# 1-Schematic_PCB__Board.net
KiCad netlist of a schematic drawn in EasyEDA
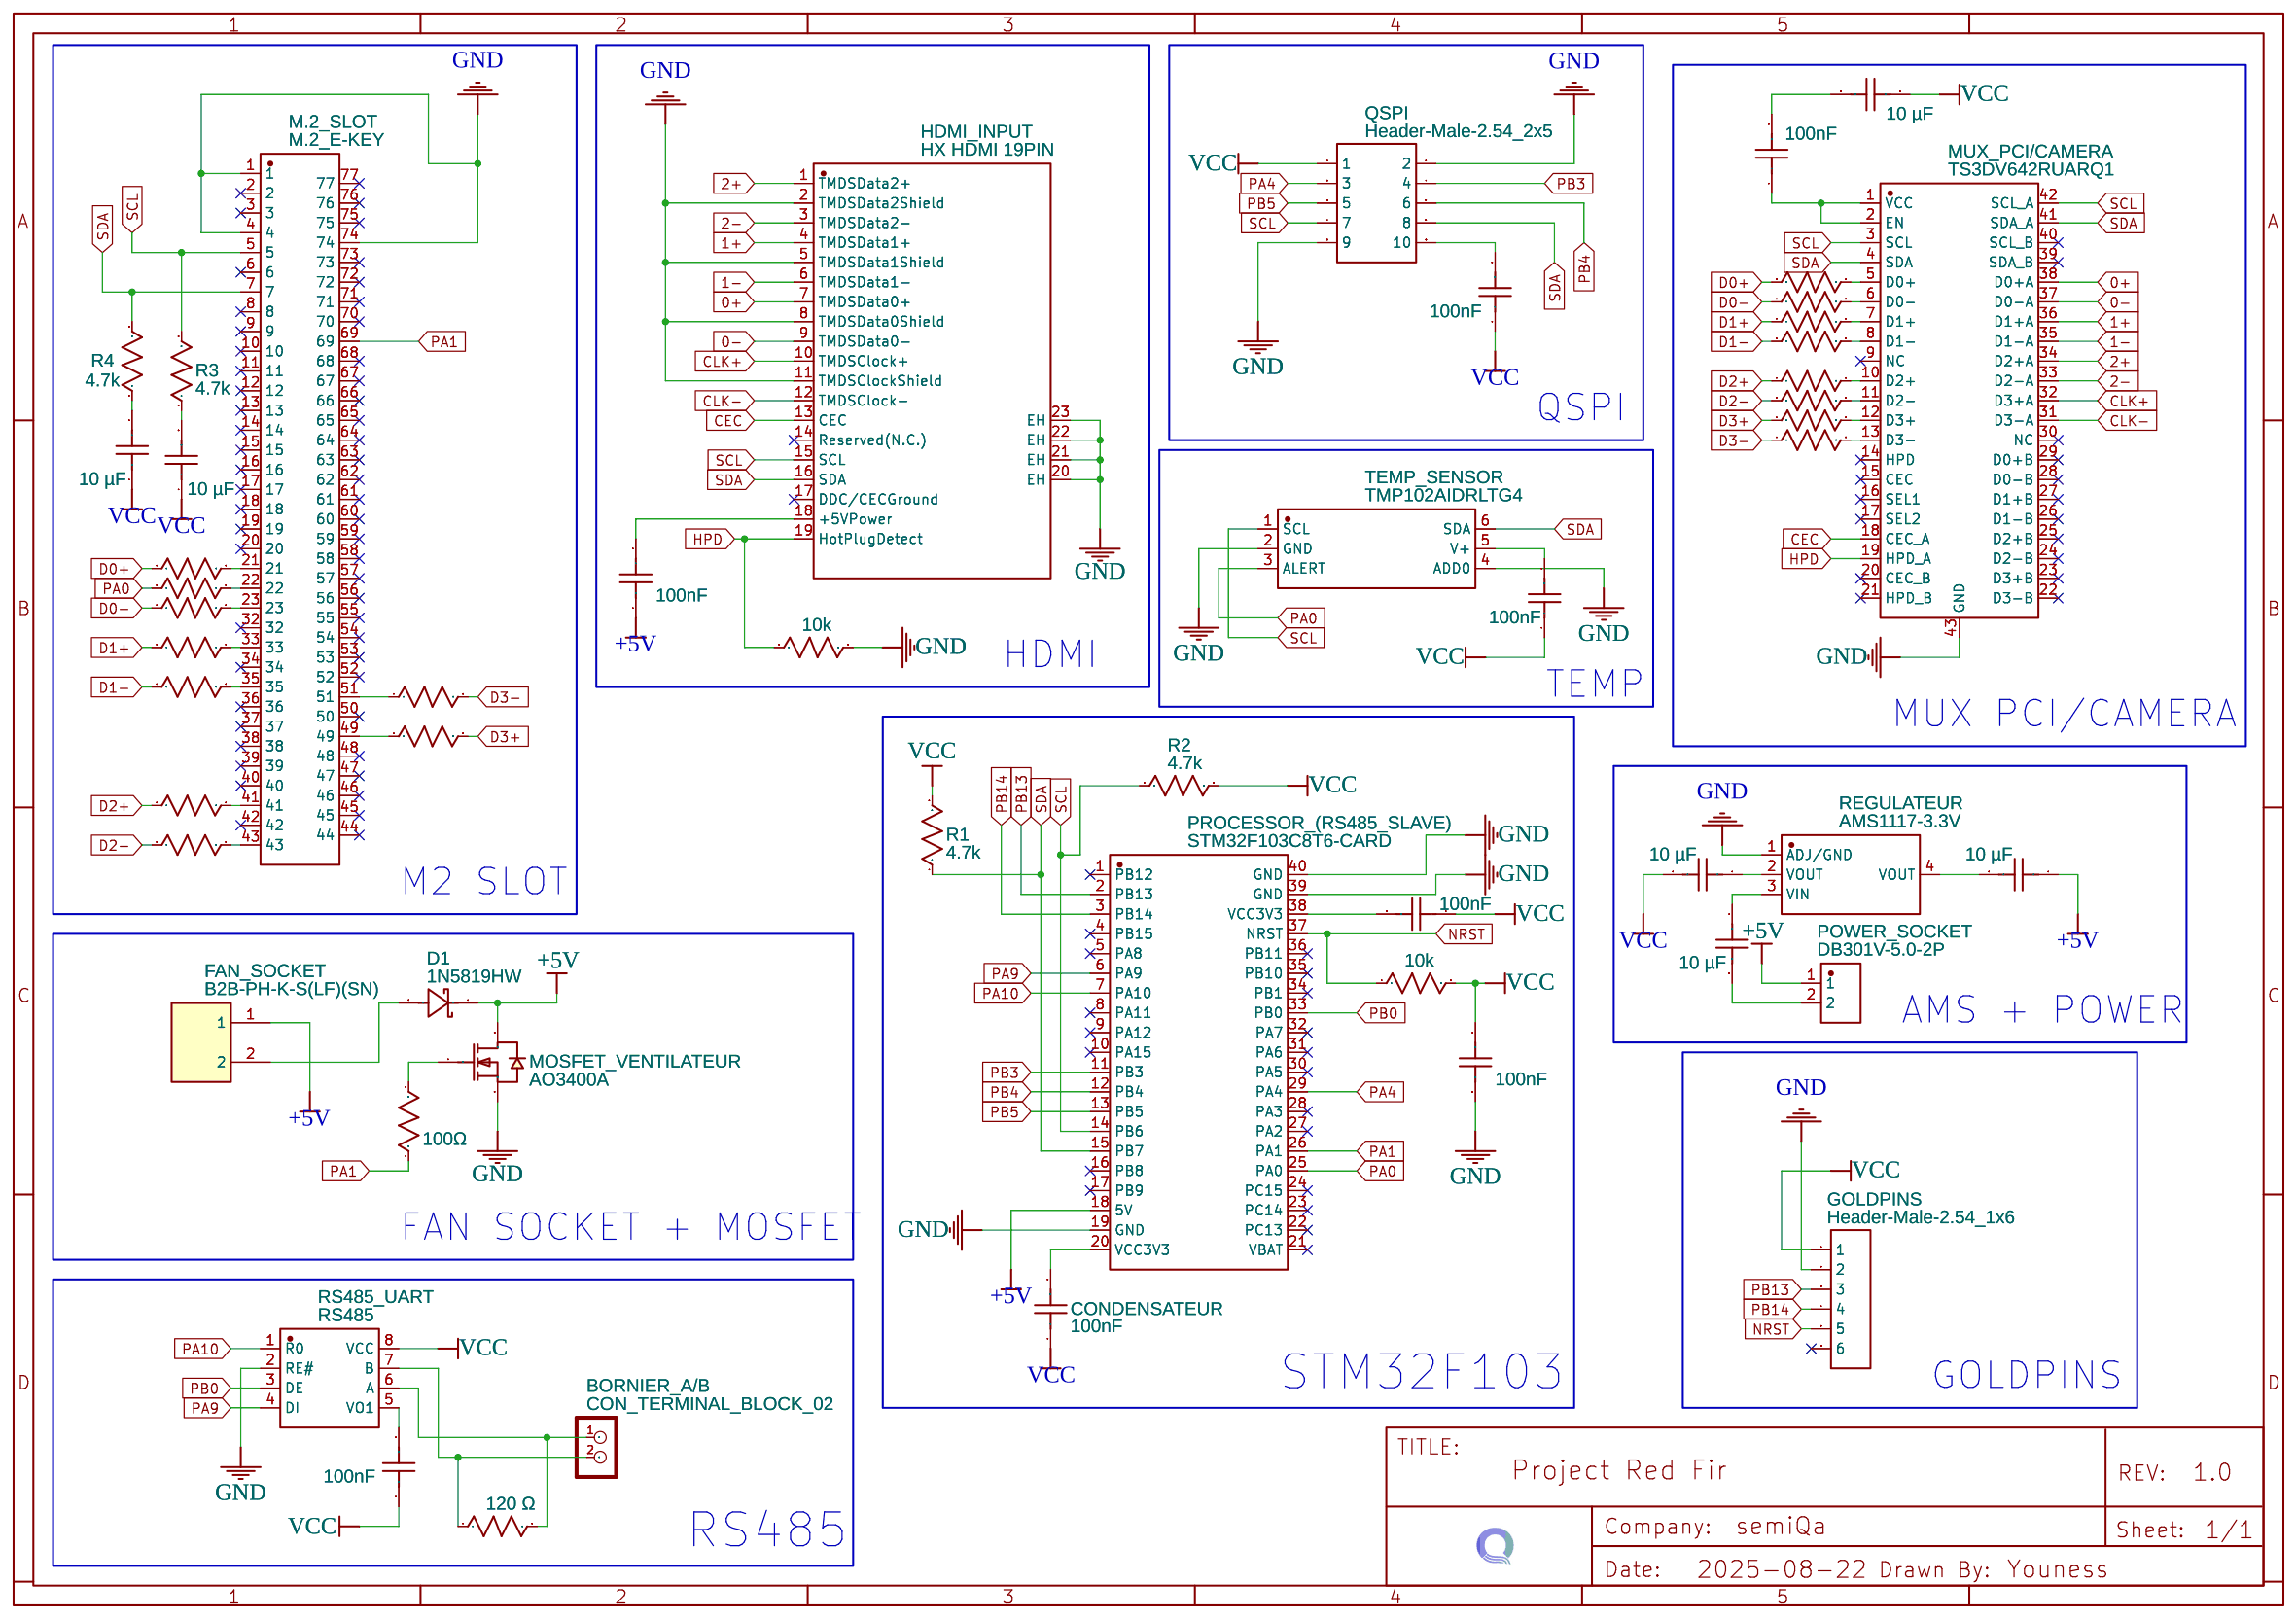
[diagram p0: schematic sheet]

(export (version "E")
  (design (tool "Eeschema 10.0.6"))
  (components
    (comp (ref "BORNIER_A/B")
      (value "CON_TERMINAL_BLOCK_02")
      (libsource (lib "") (part "CON_TERMINAL_BLOCK_02"))
    )
    (comp (ref "CONDENSATEUR")
      (value "100nF")
      (fields
        (field (name "Manufacturer Part") "CC0805KRX7R9BB104")
        (field (name "Manufacturer") "YAGEO(国巨)")
      )
      (libsource (lib "") (part "CC0805KRX7R9BB104"))
    )
    (comp (ref "CONDENSATEUR1")
      (value "100nF")
      (fields
        (field (name "Manufacturer Part") "CC0805KRX7R9BB104")
        (field (name "Manufacturer") "YAGEO(国巨)")
      )
      (libsource (lib "") (part "CC0805KRX7R9BB104"))
    )
    (comp (ref "CONDENSATEUR2")
      (value "100nF")
      (fields
        (field (name "Manufacturer Part") "CC0805KRX7R9BB104")
        (field (name "Manufacturer") "YAGEO(国巨)")
      )
      (libsource (lib "") (part "CC0805KRX7R9BB104"))
    )
    (comp (ref "CONDENSATEUR3")
      (value "100nF")
      (fields
        (field (name "Manufacturer Part") "CC0805KRX7R9BB104")
        (field (name "Manufacturer") "YAGEO(国巨)")
      )
      (libsource (lib "") (part "CC0805KRX7R9BB104"))
    )
    (comp (ref "CONDENSATEUR4")
      (value "100nF")
      (fields
        (field (name "Manufacturer Part") "CC0805KRX7R9BB104")
        (field (name "Manufacturer") "YAGEO(国巨)")
      )
      (libsource (lib "") (part "CC0805KRX7R9BB104_1"))
    )
    (comp (ref "CONDENSATEUR5")
      (value "100nF")
      (fields
        (field (name "Manufacturer Part") "CC0805KRX7R9BB104")
        (field (name "Manufacturer") "YAGEO(国巨)")
      )
      (libsource (lib "") (part "CC0805KRX7R9BB104_2"))
    )
    (comp (ref "CONDENSATEUR6")
      (value "10 µF")
      (fields
        (field (name "Manufacturer Part") "CC0805KRX7R9BB104")
        (field (name "Manufacturer") "YAGEO(国巨)")
      )
      (libsource (lib "") (part "CC0805KRX7R9BB104"))
    )
    (comp (ref "CONDENSATEUR7")
      (value "10 µF")
      (fields
        (field (name "Manufacturer Part") "CC0805KRX7R9BB104")
        (field (name "Manufacturer") "YAGEO(国巨)")
      )
      (libsource (lib "") (part "CC0805KRX7R9BB104"))
    )
    (comp (ref "CONDENSATEUR8")
      (value "10 µF")
      (fields
        (field (name "Manufacturer Part") "CC0805KRX7R9BB104")
        (field (name "Manufacturer") "YAGEO(国巨)")
      )
      (libsource (lib "") (part "CC0805KRX7R9BB104_1"))
    )
    (comp (ref "CONDENSATEUR9")
      (value "10 µF")
      (fields
        (field (name "Manufacturer Part") "CC0805KRX7R9BB104")
        (field (name "Manufacturer") "YAGEO(国巨)")
      )
      (libsource (lib "") (part "CC0805KRX7R9BB104_1"))
    )
    (comp (ref "CONDENSATEUR10")
      (value "10 µF")
      (fields
        (field (name "Manufacturer Part") "CC0805KRX7R9BB104")
        (field (name "Manufacturer") "YAGEO(国巨)")
      )
      (libsource (lib "") (part "CC0805KRX7R9BB104_2"))
    )
    (comp (ref "CONDENSATEUR11")
      (value "100nF")
      (fields
        (field (name "Manufacturer Part") "CC0805KRX7R9BB104")
        (field (name "Manufacturer") "YAGEO(国巨)")
      )
      (libsource (lib "") (part "CC0805KRX7R9BB104"))
    )
    (comp (ref "CONDENSATEUR12")
      (value "10 µF")
      (fields
        (field (name "Manufacturer Part") "CC0805KRX7R9BB104")
        (field (name "Manufacturer") "YAGEO(国巨)")
      )
      (libsource (lib "") (part "CC0805KRX7R9BB104_1"))
    )
    (comp (ref "CONDENSATEUR13")
      (value "100nF")
      (fields
        (field (name "Manufacturer Part") "CC0805KRX7R9BB104")
        (field (name "Manufacturer") "YAGEO(国巨)")
      )
      (libsource (lib "") (part "CC0805KRX7R9BB104"))
    )
    (comp (ref "D1")
      (value "1N5819HW")
      (fields (field (name "Manufacturer") "TECH PUBLIC(台舟)"))
      (libsource (lib "") (part "1N5819HW"))
    )
    (comp (ref "FAN_SOCKET")
      (value "B2B-PH-K-S(LF)(SN)")
      (fields (field (name "Manufacturer") "JST"))
      (libsource (lib "") (part "B2B-PH-K-S(LF)(SN)"))
    )
    (comp (ref "GOLDPINS")
      (value "Header-Male-2.54_1x6")
      (fields (field (name "Manufacturer Part") "2.54-1x6P直针") (field (name "Manufacturer") "BOOMELE(博穆精密)"))
      (libsource (lib "") (part "Header-Male-2.54_1x6"))
    )
    (comp (ref "HDMI_INPUT")
      (value "HX HDMI 19PIN")
      (fields (field (name "Manufacturer") "hanxia(韩下)"))
      (libsource (lib "") (part "HX HDMI 19PIN"))
    )
    (comp (ref "M.2_SLOT") (value "M.2_E-KEY") (libsource (lib "") (part "M.2_E-KEY")))
    (comp (ref "MOSFET_VENTILATEUR")
      (value "AO3400A")
      (fields (field (name "Manufacturer") "AOS"))
      (libsource (lib "") (part "AO3400A"))
    )
    (comp (ref "MUX_PCI/CAMERA")
      (value "TS3DV642RUARQ1")
      (fields (field (name "Manufacturer") "TI(德州仪器)"))
      (libsource (lib "") (part "TS3DV642RUARQ1"))
    )
    (comp (ref "POWER_SOCKET")
      (value "DB301V-5.0-2P")
      (fields
        (field (name "Manufacturer Part") "DB301V-5.0-2P-BU-S")
        (field (name "Manufacturer") "DORABO(地博电气)")
      )
      (libsource (lib "") (part "DB301V-5.0-2P"))
    )
    (comp (ref "PROCESSOR_(RS485_SLAVE)")
      (value "STM32F103C8T6-CARD")
      (fields (field (name "Manufacturer Part") "STM32F103C8T6-Card"))
      (libsource (lib "") (part "STM32F103C8T6-CARD"))
    )
    (comp (ref "QSPI")
      (value "Header-Male-2.54_2x5")
      (fields (field (name "Manufacturer Part") "2*5p排针 2.54mm"))
      (libsource (lib "") (part "Header-Male-2.54_2x5"))
    )
    (comp (ref "R1") (value "4.7k") (libsource (lib "") (part "R_0603_US_1")))
    (comp (ref "R2") (value "4.7k") (libsource (lib "") (part "R_0603_US")))
    (comp (ref "R3") (value "4.7k") (libsource (lib "") (part "R_0603_US_1")))
    (comp (ref "R4") (value "4.7k") (libsource (lib "") (part "R_0603_US_1")))
    (comp (ref "R5") (value "10k") (libsource (lib "") (part "R_0603_US")))
    (comp (ref "R6") (value "10k") (libsource (lib "") (part "R_0603_US")))
    (comp (ref "R7") (value "100Ω") (libsource (lib "") (part "R_0603_US_1")))
    (comp (ref "R8") (value "33 Ω") (libsource (lib "") (part "R_0603_US")))
    (comp (ref "R9") (value "33 Ω") (libsource (lib "") (part "R_0603_US")))
    (comp (ref "R10") (value "33 Ω") (libsource (lib "") (part "R_0603_US")))
    (comp (ref "R11") (value "33 Ω") (libsource (lib "") (part "R_0603_US")))
    (comp (ref "R12") (value "33 Ω") (libsource (lib "") (part "R_0603_US")))
    (comp (ref "R13") (value "33 Ω") (libsource (lib "") (part "R_0603_US")))
    (comp (ref "R14") (value "33 Ω") (libsource (lib "") (part "R_0603_US")))
    (comp (ref "R15") (value "33 Ω") (libsource (lib "") (part "R_0603_US")))
    (comp (ref "R16") (value "33 Ω") (libsource (lib "") (part "R_0603_US")))
    (comp (ref "R17") (value "120 Ω") (libsource (lib "") (part "R_0603_US")))
    (comp (ref "R18") (value "33 Ω") (libsource (lib "") (part "R_0603_US_2")))
    (comp (ref "R19") (value "33 Ω") (libsource (lib "") (part "R_0603_US")))
    (comp (ref "R20") (value "33 Ω") (libsource (lib "") (part "R_0603_US")))
    (comp (ref "R21") (value "33 Ω") (libsource (lib "") (part "R_0603_US")))
    (comp (ref "R22") (value "33 Ω") (libsource (lib "") (part "R_0603_US")))
    (comp (ref "R23") (value "33 Ω") (libsource (lib "") (part "R_0603_US")))
    (comp (ref "R24") (value "33 Ω") (libsource (lib "") (part "R_0603_US")))
    (comp (ref "R25") (value "33 Ω") (libsource (lib "") (part "R_0603_US")))
    (comp (ref "REGULATEUR")
      (value "AMS1117-3.3V")
      (fields (field (name "Manufacturer") "WPMtek(维攀)"))
      (libsource (lib "") (part "AMS1117-3.3V"))
    )
    (comp (ref "RS485_UART")
      (value "RS485")
      (fields (field (name "Manufacturer") "GR(国睿)"))
      (libsource (lib "") (part "RS485"))
    )
    (comp (ref "TEMP_SENSOR")
      (value "TMP102AIDRLTG4")
      (fields (field (name "Manufacturer") "TI(德州仪器)"))
      (libsource (lib "") (part "TMP102AIDRLTG4"))
    )
  )
  (nets
    (net (code "1") (name "+5V") (class "Default")
      (node (ref "CONDENSATEUR11") (pin "1") (pinfunction "1_1") (pintype "unspecified"))
      (node (ref "CONDENSATEUR8") (pin "1") (pinfunction "1_1") (pintype "unspecified"))
      (node (ref "D1") (pin "1") (pinfunction "K_1") (pintype "unspecified"))
      (node (ref "FAN_SOCKET") (pin "1") (pinfunction "1_1") (pintype "input"))
      (node (ref "MOSFET_VENTILATEUR") (pin "3") (pinfunction "D_3") (pintype "unspecified"))
      (node (ref "POWER_SOCKET") (pin "1") (pinfunction "1_1") (pintype "unspecified"))
      (node (ref "PROCESSOR_(RS485_SLAVE)") (pin "18") (pinfunction "5V_18") (pintype "unspecified"))
    )
    (net (code "2") (name "0+") (class "Default")
      (node (ref "HDMI_INPUT") (pin "7") (pinfunction "TMDSData0+_7") (pintype "unspecified"))
      (node (ref "MUX_PCI/CAMERA") (pin "38") (pinfunction "D0+A_38") (pintype "unspecified"))
    )
    (net (code "3") (name "0-") (class "Default")
      (node (ref "HDMI_INPUT") (pin "9") (pinfunction "TMDSData0-_9") (pintype "unspecified"))
      (node (ref "MUX_PCI/CAMERA") (pin "37") (pinfunction "D0-A_37") (pintype "unspecified"))
    )
    (net (code "4") (name "1+") (class "Default")
      (node (ref "HDMI_INPUT") (pin "4") (pinfunction "TMDSData1+_4") (pintype "unspecified"))
      (node (ref "MUX_PCI/CAMERA") (pin "36") (pinfunction "D1+A_36") (pintype "unspecified"))
    )
    (net (code "5") (name "1-") (class "Default")
      (node (ref "HDMI_INPUT") (pin "6") (pinfunction "TMDSData1-_6") (pintype "unspecified"))
      (node (ref "MUX_PCI/CAMERA") (pin "35") (pinfunction "D1-A_35") (pintype "unspecified"))
    )
    (net (code "6") (name "2+") (class "Default")
      (node (ref "HDMI_INPUT") (pin "1") (pinfunction "TMDSData2+_1") (pintype "unspecified"))
      (node (ref "MUX_PCI/CAMERA") (pin "34") (pinfunction "D2+A_34") (pintype "unspecified"))
    )
    (net (code "7") (name "2-") (class "Default")
      (node (ref "HDMI_INPUT") (pin "3") (pinfunction "TMDSData2-_3") (pintype "unspecified"))
      (node (ref "MUX_PCI/CAMERA") (pin "33") (pinfunction "D2-A_33") (pintype "unspecified"))
    )
    (net (code "8") (name "CEC") (class "Default")
      (node (ref "HDMI_INPUT") (pin "13") (pinfunction "CEC_13") (pintype "unspecified"))
      (node (ref "MUX_PCI/CAMERA") (pin "18") (pinfunction "CEC_A_18") (pintype "unspecified"))
    )
    (net (code "9") (name "CLK+") (class "Default")
      (node (ref "HDMI_INPUT") (pin "10") (pinfunction "TMDSClock+_10") (pintype "unspecified"))
      (node (ref "MUX_PCI/CAMERA") (pin "32") (pinfunction "D3+A_32") (pintype "unspecified"))
    )
    (net (code "10") (name "CLK-") (class "Default")
      (node (ref "HDMI_INPUT") (pin "12") (pinfunction "TMDSClock-_12") (pintype "unspecified"))
      (node (ref "MUX_PCI/CAMERA") (pin "31") (pinfunction "D3-A_31") (pintype "unspecified"))
    )
    (net (code "11") (name "D0+") (class "Default")
      (node (ref "R18") (pin "2") (pinfunction "2_2") (pintype "unspecified"))
      (node (ref "R8") (pin "1") (pinfunction "1_1") (pintype "unspecified"))
    )
    (net (code "12") (name "D0-") (class "Default")
      (node (ref "R10") (pin "1") (pinfunction "1_1") (pintype "unspecified"))
      (node (ref "R19") (pin "1") (pinfunction "1_1") (pintype "unspecified"))
    )
    (net (code "13") (name "D1+") (class "Default")
      (node (ref "R11") (pin "1") (pinfunction "1_1") (pintype "unspecified"))
      (node (ref "R20") (pin "1") (pinfunction "1_1") (pintype "unspecified"))
    )
    (net (code "14") (name "D1-") (class "Default")
      (node (ref "R12") (pin "1") (pinfunction "1_1") (pintype "unspecified"))
      (node (ref "R21") (pin "1") (pinfunction "1_1") (pintype "unspecified"))
    )
    (net (code "15") (name "D2+") (class "Default")
      (node (ref "R15") (pin "1") (pinfunction "1_1") (pintype "unspecified"))
      (node (ref "R22") (pin "1") (pinfunction "1_1") (pintype "unspecified"))
    )
    (net (code "16") (name "D2-") (class "Default")
      (node (ref "R16") (pin "1") (pinfunction "1_1") (pintype "unspecified"))
      (node (ref "R23") (pin "1") (pinfunction "1_1") (pintype "unspecified"))
    )
    (net (code "17") (name "D3+") (class "Default")
      (node (ref "R14") (pin "2") (pinfunction "2_2") (pintype "unspecified"))
      (node (ref "R24") (pin "1") (pinfunction "1_1") (pintype "unspecified"))
    )
    (net (code "18") (name "D3-") (class "Default")
      (node (ref "R13") (pin "2") (pinfunction "2_2") (pintype "unspecified"))
      (node (ref "R25") (pin "1") (pinfunction "1_1") (pintype "unspecified"))
    )
    (net (code "19") (name "GND") (class "Default")
      (node (ref "CONDENSATEUR5") (pin "2") (pinfunction "2_2") (pintype "unspecified"))
      (node (ref "GOLDPINS") (pin "2") (pinfunction "2_2") (pintype "input"))
      (node (ref "HDMI_INPUT") (pin "11") (pinfunction "TMDSClockShield_11") (pintype "unspecified"))
      (node (ref "HDMI_INPUT") (pin "2") (pinfunction "TMDSData2Shield_2") (pintype "unspecified"))
      (node (ref "HDMI_INPUT") (pin "20") (pinfunction "EH_20") (pintype "unspecified"))
      (node (ref "HDMI_INPUT") (pin "21") (pinfunction "EH_21") (pintype "unspecified"))
      (node (ref "HDMI_INPUT") (pin "22") (pinfunction "EH_22") (pintype "unspecified"))
      (node (ref "HDMI_INPUT") (pin "23") (pinfunction "EH_23") (pintype "unspecified"))
      (node (ref "HDMI_INPUT") (pin "5") (pinfunction "TMDSData1Shield_5") (pintype "unspecified"))
      (node (ref "HDMI_INPUT") (pin "8") (pinfunction "TMDSData0Shield_8") (pintype "unspecified"))
      (node (ref "M.2_SLOT") (pin "1") (pinfunction "1_1") (pintype "unspecified"))
      (node (ref "M.2_SLOT") (pin "4") (pinfunction "4_4") (pintype "unspecified"))
      (node (ref "M.2_SLOT") (pin "74") (pinfunction "74_74") (pintype "unspecified"))
      (node (ref "MOSFET_VENTILATEUR") (pin "2") (pinfunction "S_2") (pintype "unspecified"))
      (node (ref "MUX_PCI/CAMERA") (pin "43") (pinfunction "GND_43") (pintype "unspecified"))
      (node (ref "PROCESSOR_(RS485_SLAVE)") (pin "19") (pinfunction "GND_19") (pintype "unspecified"))
      (node (ref "PROCESSOR_(RS485_SLAVE)") (pin "39") (pinfunction "GND_39") (pintype "unspecified"))
      (node (ref "PROCESSOR_(RS485_SLAVE)") (pin "40") (pinfunction "GND_40") (pintype "unspecified"))
      (node (ref "QSPI") (pin "2") (pinfunction "2_2") (pintype "input"))
      (node (ref "QSPI") (pin "9") (pinfunction "9_9") (pintype "input"))
      (node (ref "R6") (pin "2") (pinfunction "2_2") (pintype "unspecified"))
      (node (ref "REGULATEUR") (pin "1") (pinfunction "ADJ/GND_1") (pintype "unspecified"))
      (node (ref "RS485_UART") (pin "2") (pinfunction "RE#_2") (pintype "unspecified"))
      (node (ref "TEMP_SENSOR") (pin "2") (pinfunction "GND_2") (pintype "unspecified"))
      (node (ref "TEMP_SENSOR") (pin "4") (pinfunction "ADD0_4") (pintype "unspecified"))
    )
    (net (code "20") (name "HPD") (class "Default")
      (node (ref "HDMI_INPUT") (pin "19") (pinfunction "HotPlugDetect_19") (pintype "unspecified"))
      (node (ref "MUX_PCI/CAMERA") (pin "19") (pinfunction "HPD_A_19") (pintype "unspecified"))
      (node (ref "R6") (pin "1") (pinfunction "1_1") (pintype "unspecified"))
    )
    (net (code "21") (name "NRST") (class "Default")
      (node (ref "GOLDPINS") (pin "5") (pinfunction "5_5") (pintype "input"))
      (node (ref "PROCESSOR_(RS485_SLAVE)") (pin "37") (pinfunction "NRST_37") (pintype "unspecified"))
      (node (ref "R5") (pin "1") (pinfunction "1_1") (pintype "unspecified"))
    )
    (net (code "22") (name "Net-(CONDENSATEUR-Pad2)") (class "Default")
      (node (ref "CONDENSATEUR") (pin "2") (pinfunction "2_2") (pintype "unspecified"))
      (node (ref "PROCESSOR_(RS485_SLAVE)") (pin "20") (pinfunction "VCC3V3_20") (pintype "unspecified"))
    )
    (net (code "23") (name "Net-(CONDENSATEUR1-Pad2)") (class "Default")
      (node (ref "CONDENSATEUR1") (pin "2") (pinfunction "2_2") (pintype "unspecified"))
      (node (ref "QSPI") (pin "10") (pinfunction "10_10") (pintype "input"))
    )
    (net (code "24") (name "Net-(CONDENSATEUR4-Pad2)") (class "Default")
      (node (ref "CONDENSATEUR4") (pin "2") (pinfunction "2_2") (pintype "unspecified"))
      (node (ref "PROCESSOR_(RS485_SLAVE)") (pin "38") (pinfunction "VCC3V3_38") (pintype "unspecified"))
    )
    (net (code "25") (name "Net-(CONDENSATEUR6-Pad2)") (class "Default")
      (node (ref "CONDENSATEUR6") (pin "2") (pinfunction "2_2") (pintype "unspecified"))
      (node (ref "R4") (pin "1") (pinfunction "1_1") (pintype "unspecified"))
    )
    (net (code "26") (name "Net-(CONDENSATEUR7-Pad2)") (class "Default")
      (node (ref "CONDENSATEUR7") (pin "2") (pinfunction "2_2") (pintype "unspecified"))
      (node (ref "R3") (pin "1") (pinfunction "1_1") (pintype "unspecified"))
    )
    (net (code "27") (name "Net-(CONDENSATEUR8-Pad2)") (class "Default")
      (node (ref "CONDENSATEUR8") (pin "2") (pinfunction "2_2") (pintype "unspecified"))
      (node (ref "REGULATEUR") (pin "4") (pinfunction "VOUT_4") (pintype "unspecified"))
    )
    (net (code "28") (name "Net-(CONDENSATEUR9-Pad1)") (class "Default")
      (node (ref "CONDENSATEUR9") (pin "1") (pinfunction "1_1") (pintype "unspecified"))
      (node (ref "REGULATEUR") (pin "2") (pinfunction "VOUT_2") (pintype "unspecified"))
    )
    (net (code "29") (name "Net-(CONDENSATEUR10-Pad2)") (class "Default")
      (node (ref "CONDENSATEUR10") (pin "2") (pinfunction "2_2") (pintype "unspecified"))
      (node (ref "POWER_SOCKET") (pin "2") (pinfunction "2_2") (pintype "unspecified"))
    )
    (net (code "30") (name "Net-(CONDENSATEUR12-Pad2)") (class "Default")
      (node (ref "CONDENSATEUR12") (pin "2") (pinfunction "2_2") (pintype "unspecified"))
      (node (ref "CONDENSATEUR2") (pin "2") (pinfunction "2_2") (pintype "unspecified"))
    )
    (net (code "31") (name "Net-(D1-A)") (class "Default")
      (node (ref "D1") (pin "2") (pinfunction "A_2") (pintype "unspecified"))
      (node (ref "FAN_SOCKET") (pin "2") (pinfunction "2_2") (pintype "input"))
    )
    (net (code "32") (name "Net-(HDMI_INPUT-+5VPower)") (class "Default")
      (node (ref "CONDENSATEUR11") (pin "2") (pinfunction "2_2") (pintype "unspecified"))
      (node (ref "HDMI_INPUT") (pin "18") (pinfunction "+5VPower_18") (pintype "unspecified"))
    )
    (net (code "33") (name "Net-(M.2_SLOT-Pad21)") (class "Default")
      (node (ref "M.2_SLOT") (pin "21") (pinfunction "21_21") (pintype "unspecified"))
      (node (ref "R8") (pin "2") (pinfunction "2_2") (pintype "unspecified"))
    )
    (net (code "34") (name "Net-(M.2_SLOT-Pad22)") (class "Default")
      (node (ref "M.2_SLOT") (pin "22") (pinfunction "22_22") (pintype "unspecified"))
      (node (ref "R9") (pin "2") (pinfunction "2_2") (pintype "unspecified"))
    )
    (net (code "35") (name "Net-(M.2_SLOT-Pad23)") (class "Default")
      (node (ref "M.2_SLOT") (pin "23") (pinfunction "23_23") (pintype "unspecified"))
      (node (ref "R10") (pin "2") (pinfunction "2_2") (pintype "unspecified"))
    )
    (net (code "36") (name "Net-(M.2_SLOT-Pad33)") (class "Default")
      (node (ref "M.2_SLOT") (pin "33") (pinfunction "33_33") (pintype "unspecified"))
      (node (ref "R11") (pin "2") (pinfunction "2_2") (pintype "unspecified"))
    )
    (net (code "37") (name "Net-(M.2_SLOT-Pad35)") (class "Default")
      (node (ref "M.2_SLOT") (pin "35") (pinfunction "35_35") (pintype "unspecified"))
      (node (ref "R12") (pin "2") (pinfunction "2_2") (pintype "unspecified"))
    )
    (net (code "38") (name "Net-(M.2_SLOT-Pad41)") (class "Default")
      (node (ref "M.2_SLOT") (pin "41") (pinfunction "41_41") (pintype "unspecified"))
      (node (ref "R15") (pin "2") (pinfunction "2_2") (pintype "unspecified"))
    )
    (net (code "39") (name "Net-(M.2_SLOT-Pad43)") (class "Default")
      (node (ref "M.2_SLOT") (pin "43") (pinfunction "43_43") (pintype "unspecified"))
      (node (ref "R16") (pin "2") (pinfunction "2_2") (pintype "unspecified"))
    )
    (net (code "40") (name "Net-(M.2_SLOT-Pad49)") (class "Default")
      (node (ref "M.2_SLOT") (pin "49") (pinfunction "49_49") (pintype "unspecified"))
      (node (ref "R14") (pin "1") (pinfunction "1_1") (pintype "unspecified"))
    )
    (net (code "41") (name "Net-(M.2_SLOT-Pad51)") (class "Default")
      (node (ref "M.2_SLOT") (pin "51") (pinfunction "51_51") (pintype "unspecified"))
      (node (ref "R13") (pin "1") (pinfunction "1_1") (pintype "unspecified"))
    )
    (net (code "42") (name "Net-(MOSFET_VENTILATEUR-G)") (class "Default")
      (node (ref "MOSFET_VENTILATEUR") (pin "1") (pinfunction "G_1") (pintype "unspecified"))
      (node (ref "R7") (pin "2") (pinfunction "2_2") (pintype "unspecified"))
    )
    (net (code "43") (name "Net-(MUX_PCI/CAMERA-D0+)") (class "Default")
      (node (ref "MUX_PCI/CAMERA") (pin "5") (pinfunction "D0+_5") (pintype "unspecified"))
      (node (ref "R18") (pin "1") (pinfunction "1_1") (pintype "unspecified"))
    )
    (net (code "44") (name "Net-(MUX_PCI/CAMERA-D0-)") (class "Default")
      (node (ref "MUX_PCI/CAMERA") (pin "6") (pinfunction "D0-_6") (pintype "unspecified"))
      (node (ref "R19") (pin "2") (pinfunction "2_2") (pintype "unspecified"))
    )
    (net (code "45") (name "Net-(MUX_PCI/CAMERA-D1+)") (class "Default")
      (node (ref "MUX_PCI/CAMERA") (pin "7") (pinfunction "D1+_7") (pintype "unspecified"))
      (node (ref "R20") (pin "2") (pinfunction "2_2") (pintype "unspecified"))
    )
    (net (code "46") (name "Net-(MUX_PCI/CAMERA-D1-)") (class "Default")
      (node (ref "MUX_PCI/CAMERA") (pin "8") (pinfunction "D1-_8") (pintype "unspecified"))
      (node (ref "R21") (pin "2") (pinfunction "2_2") (pintype "unspecified"))
    )
    (net (code "47") (name "Net-(MUX_PCI/CAMERA-D2+)") (class "Default")
      (node (ref "MUX_PCI/CAMERA") (pin "10") (pinfunction "D2+_10") (pintype "unspecified"))
      (node (ref "R22") (pin "2") (pinfunction "2_2") (pintype "unspecified"))
    )
    (net (code "48") (name "Net-(MUX_PCI/CAMERA-D2-)") (class "Default")
      (node (ref "MUX_PCI/CAMERA") (pin "11") (pinfunction "D2-_11") (pintype "unspecified"))
      (node (ref "R23") (pin "2") (pinfunction "2_2") (pintype "unspecified"))
    )
    (net (code "49") (name "Net-(MUX_PCI/CAMERA-D3+)") (class "Default")
      (node (ref "MUX_PCI/CAMERA") (pin "12") (pinfunction "D3+_12") (pintype "unspecified"))
      (node (ref "R24") (pin "2") (pinfunction "2_2") (pintype "unspecified"))
    )
    (net (code "50") (name "Net-(MUX_PCI/CAMERA-D3-)") (class "Default")
      (node (ref "MUX_PCI/CAMERA") (pin "13") (pinfunction "D3-_13") (pintype "unspecified"))
      (node (ref "R25") (pin "2") (pinfunction "2_2") (pintype "unspecified"))
    )
    (net (code "51") (name "Net-(MUX_PCI/CAMERA-EN)") (class "Default")
      (node (ref "CONDENSATEUR2") (pin "1") (pinfunction "1_1") (pintype "unspecified"))
      (node (ref "MUX_PCI/CAMERA") (pin "1") (pinfunction "VCC_1") (pintype "unspecified"))
      (node (ref "MUX_PCI/CAMERA") (pin "2") (pinfunction "EN_2") (pintype "unspecified"))
    )
    (net (code "52") (name "Net-(REGULATEUR-VIN)") (class "Default")
      (node (ref "CONDENSATEUR10") (pin "1") (pinfunction "1_1") (pintype "unspecified"))
      (node (ref "REGULATEUR") (pin "3") (pinfunction "VIN_3") (pintype "unspecified"))
    )
    (net (code "53") (name "Net-(RS485_UART-A)") (class "Default")
      (node (ref "BORNIER_A/B") (pin "1") (pinfunction "1_1") (pintype "unspecified"))
      (node (ref "R17") (pin "2") (pinfunction "2_2") (pintype "unspecified"))
      (node (ref "RS485_UART") (pin "6") (pinfunction "A_6") (pintype "unspecified"))
    )
    (net (code "54") (name "Net-(RS485_UART-B)") (class "Default")
      (node (ref "BORNIER_A/B") (pin "2") (pinfunction "2_2") (pintype "unspecified"))
      (node (ref "R17") (pin "1") (pinfunction "1_1") (pintype "unspecified"))
      (node (ref "RS485_UART") (pin "7") (pinfunction "B_7") (pintype "unspecified"))
    )
    (net (code "55") (name "Net-(RS485_UART-VO1)") (class "Default")
      (node (ref "CONDENSATEUR13") (pin "2") (pinfunction "2_2") (pintype "unspecified"))
      (node (ref "RS485_UART") (pin "5") (pinfunction "VO1_5") (pintype "unspecified"))
    )
    (net (code "56") (name "Net-(TEMP_SENSOR-V+)") (class "Default")
      (node (ref "CONDENSATEUR3") (pin "2") (pinfunction "2_2") (pintype "unspecified"))
      (node (ref "TEMP_SENSOR") (pin "5") (pinfunction "V+_5") (pintype "unspecified"))
    )
    (net (code "57") (name "PA0") (class "Default")
      (node (ref "PROCESSOR_(RS485_SLAVE)") (pin "25") (pinfunction "PA0_25") (pintype "unspecified"))
      (node (ref "R9") (pin "1") (pinfunction "1_1") (pintype "unspecified"))
      (node (ref "TEMP_SENSOR") (pin "3") (pinfunction "ALERT_3") (pintype "unspecified"))
    )
    (net (code "58") (name "PA1") (class "Default")
      (node (ref "M.2_SLOT") (pin "69") (pinfunction "69_69") (pintype "unspecified"))
      (node (ref "PROCESSOR_(RS485_SLAVE)") (pin "26") (pinfunction "PA1_26") (pintype "unspecified"))
      (node (ref "R7") (pin "1") (pinfunction "1_1") (pintype "unspecified"))
    )
    (net (code "59") (name "PA4") (class "Default")
      (node (ref "PROCESSOR_(RS485_SLAVE)") (pin "29") (pinfunction "PA4_29") (pintype "unspecified"))
      (node (ref "QSPI") (pin "3") (pinfunction "3_3") (pintype "input"))
    )
    (net (code "60") (name "PA9") (class "Default")
      (node (ref "PROCESSOR_(RS485_SLAVE)") (pin "6") (pinfunction "PA9_6") (pintype "unspecified"))
      (node (ref "RS485_UART") (pin "4") (pinfunction "DI_4") (pintype "unspecified"))
    )
    (net (code "61") (name "PA10") (class "Default")
      (node (ref "PROCESSOR_(RS485_SLAVE)") (pin "7") (pinfunction "PA10_7") (pintype "unspecified"))
      (node (ref "RS485_UART") (pin "1") (pinfunction "R0_1") (pintype "unspecified"))
    )
    (net (code "62") (name "PB0") (class "Default")
      (node (ref "PROCESSOR_(RS485_SLAVE)") (pin "33") (pinfunction "PB0_33") (pintype "unspecified"))
      (node (ref "RS485_UART") (pin "3") (pinfunction "DE_3") (pintype "unspecified"))
    )
    (net (code "63") (name "PB3") (class "Default")
      (node (ref "PROCESSOR_(RS485_SLAVE)") (pin "11") (pinfunction "PB3_11") (pintype "unspecified"))
      (node (ref "QSPI") (pin "4") (pinfunction "4_4") (pintype "input"))
    )
    (net (code "64") (name "PB4") (class "Default")
      (node (ref "PROCESSOR_(RS485_SLAVE)") (pin "12") (pinfunction "PB4_12") (pintype "unspecified"))
      (node (ref "QSPI") (pin "6") (pinfunction "6_6") (pintype "input"))
    )
    (net (code "65") (name "PB5") (class "Default")
      (node (ref "PROCESSOR_(RS485_SLAVE)") (pin "13") (pinfunction "PB5_13") (pintype "unspecified"))
      (node (ref "QSPI") (pin "5") (pinfunction "5_5") (pintype "input"))
    )
    (net (code "66") (name "PB13") (class "Default")
      (node (ref "GOLDPINS") (pin "3") (pinfunction "3_3") (pintype "input"))
      (node (ref "PROCESSOR_(RS485_SLAVE)") (pin "2") (pinfunction "PB13_2") (pintype "unspecified"))
    )
    (net (code "67") (name "PB14") (class "Default")
      (node (ref "GOLDPINS") (pin "4") (pinfunction "4_4") (pintype "input"))
      (node (ref "PROCESSOR_(RS485_SLAVE)") (pin "3") (pinfunction "PB14_3") (pintype "unspecified"))
    )
    (net (code "68") (name "SCL") (class "Default")
      (node (ref "HDMI_INPUT") (pin "15") (pinfunction "SCL_15") (pintype "unspecified"))
      (node (ref "M.2_SLOT") (pin "5") (pinfunction "5_5") (pintype "unspecified"))
      (node (ref "MUX_PCI/CAMERA") (pin "3") (pinfunction "SCL_3") (pintype "unspecified"))
      (node (ref "MUX_PCI/CAMERA") (pin "42") (pinfunction "SCL_A_42") (pintype "unspecified"))
      (node (ref "PROCESSOR_(RS485_SLAVE)") (pin "14") (pinfunction "PB6_14") (pintype "unspecified"))
      (node (ref "QSPI") (pin "7") (pinfunction "7_7") (pintype "input"))
      (node (ref "R2") (pin "1") (pinfunction "1_1") (pintype "unspecified"))
      (node (ref "R3") (pin "2") (pinfunction "2_2") (pintype "unspecified"))
      (node (ref "TEMP_SENSOR") (pin "1") (pinfunction "SCL_1") (pintype "unspecified"))
    )
    (net (code "69") (name "SDA") (class "Default")
      (node (ref "HDMI_INPUT") (pin "16") (pinfunction "SDA_16") (pintype "unspecified"))
      (node (ref "M.2_SLOT") (pin "7") (pinfunction "7_7") (pintype "unspecified"))
      (node (ref "MUX_PCI/CAMERA") (pin "4") (pinfunction "SDA_4") (pintype "unspecified"))
      (node (ref "MUX_PCI/CAMERA") (pin "41") (pinfunction "SDA_A_41") (pintype "unspecified"))
      (node (ref "PROCESSOR_(RS485_SLAVE)") (pin "15") (pinfunction "PB7_15") (pintype "unspecified"))
      (node (ref "QSPI") (pin "8") (pinfunction "8_8") (pintype "input"))
      (node (ref "R1") (pin "1") (pinfunction "1_1") (pintype "unspecified"))
      (node (ref "R4") (pin "2") (pinfunction "2_2") (pintype "unspecified"))
      (node (ref "TEMP_SENSOR") (pin "6") (pinfunction "SDA_6") (pintype "unspecified"))
    )
    (net (code "70") (name "VCC") (class "Default")
      (node (ref "CONDENSATEUR") (pin "1") (pinfunction "1_1") (pintype "unspecified"))
      (node (ref "CONDENSATEUR1") (pin "1") (pinfunction "1_1") (pintype "unspecified"))
      (node (ref "CONDENSATEUR12") (pin "1") (pinfunction "1_1") (pintype "unspecified"))
      (node (ref "CONDENSATEUR13") (pin "1") (pinfunction "1_1") (pintype "unspecified"))
      (node (ref "CONDENSATEUR3") (pin "1") (pinfunction "1_1") (pintype "unspecified"))
      (node (ref "CONDENSATEUR4") (pin "1") (pinfunction "1_1") (pintype "unspecified"))
      (node (ref "CONDENSATEUR5") (pin "1") (pinfunction "1_1") (pintype "unspecified"))
      (node (ref "CONDENSATEUR6") (pin "1") (pinfunction "1_1") (pintype "unspecified"))
      (node (ref "CONDENSATEUR7") (pin "1") (pinfunction "1_1") (pintype "unspecified"))
      (node (ref "CONDENSATEUR9") (pin "2") (pinfunction "2_2") (pintype "unspecified"))
      (node (ref "GOLDPINS") (pin "1") (pinfunction "1_1") (pintype "input"))
      (node (ref "QSPI") (pin "1") (pinfunction "1_1") (pintype "input"))
      (node (ref "R1") (pin "2") (pinfunction "2_2") (pintype "unspecified"))
      (node (ref "R2") (pin "2") (pinfunction "2_2") (pintype "unspecified"))
      (node (ref "R5") (pin "2") (pinfunction "2_2") (pintype "unspecified"))
      (node (ref "RS485_UART") (pin "8") (pinfunction "VCC_8") (pintype "unspecified"))
    )
    (net (code "71") (name "unconnected-(GOLDPINS-Pad6)") (class "Default")
      (node (ref "GOLDPINS") (pin "6") (pinfunction "6_6") (pintype "input+no_connect"))
    )
    (net (code "72") (name "unconnected-(HDMI_INPUT-DDC{slash}CECGround-Pad17)") (class "Default")
      (node (ref "HDMI_INPUT") (pin "17") (pinfunction "DDC/CECGround_17") (pintype "unspecified+no_connect"))
    )
    (net (code "73") (name "unconnected-(HDMI_INPUT-Reserved(N.C.)-Pad14)") (class "Default")
      (node (ref "HDMI_INPUT") (pin "14") (pinfunction "Reserved(N.C.)_14") (pintype "unspecified+no_connect"))
    )
    (net (code "74") (name "unconnected-(M.2_SLOT-Pad2)") (class "Default")
      (node (ref "M.2_SLOT") (pin "2") (pinfunction "2_2") (pintype "unspecified+no_connect"))
    )
    (net (code "75") (name "unconnected-(M.2_SLOT-Pad3)") (class "Default")
      (node (ref "M.2_SLOT") (pin "3") (pinfunction "3_3") (pintype "unspecified+no_connect"))
    )
    (net (code "76") (name "unconnected-(M.2_SLOT-Pad6)") (class "Default")
      (node (ref "M.2_SLOT") (pin "6") (pinfunction "6_6") (pintype "unspecified+no_connect"))
    )
    (net (code "77") (name "unconnected-(M.2_SLOT-Pad8)") (class "Default")
      (node (ref "M.2_SLOT") (pin "8") (pinfunction "8_8") (pintype "unspecified+no_connect"))
    )
    (net (code "78") (name "unconnected-(M.2_SLOT-Pad9)") (class "Default")
      (node (ref "M.2_SLOT") (pin "9") (pinfunction "9_9") (pintype "unspecified+no_connect"))
    )
    (net (code "79") (name "unconnected-(M.2_SLOT-Pad10)") (class "Default")
      (node (ref "M.2_SLOT") (pin "10") (pinfunction "10_10") (pintype "unspecified+no_connect"))
    )
    (net (code "80") (name "unconnected-(M.2_SLOT-Pad11)") (class "Default")
      (node (ref "M.2_SLOT") (pin "11") (pinfunction "11_11") (pintype "unspecified+no_connect"))
    )
    (net (code "81") (name "unconnected-(M.2_SLOT-Pad12)") (class "Default")
      (node (ref "M.2_SLOT") (pin "12") (pinfunction "12_12") (pintype "unspecified+no_connect"))
    )
    (net (code "82") (name "unconnected-(M.2_SLOT-Pad13)") (class "Default")
      (node (ref "M.2_SLOT") (pin "13") (pinfunction "13_13") (pintype "unspecified+no_connect"))
    )
    (net (code "83") (name "unconnected-(M.2_SLOT-Pad14)") (class "Default")
      (node (ref "M.2_SLOT") (pin "14") (pinfunction "14_14") (pintype "unspecified+no_connect"))
    )
    (net (code "84") (name "unconnected-(M.2_SLOT-Pad15)") (class "Default")
      (node (ref "M.2_SLOT") (pin "15") (pinfunction "15_15") (pintype "unspecified+no_connect"))
    )
    (net (code "85") (name "unconnected-(M.2_SLOT-Pad16)") (class "Default")
      (node (ref "M.2_SLOT") (pin "16") (pinfunction "16_16") (pintype "unspecified+no_connect"))
    )
    (net (code "86") (name "unconnected-(M.2_SLOT-Pad17)") (class "Default")
      (node (ref "M.2_SLOT") (pin "17") (pinfunction "17_17") (pintype "unspecified+no_connect"))
    )
    (net (code "87") (name "unconnected-(M.2_SLOT-Pad18)") (class "Default")
      (node (ref "M.2_SLOT") (pin "18") (pinfunction "18_18") (pintype "unspecified+no_connect"))
    )
    (net (code "88") (name "unconnected-(M.2_SLOT-Pad19)") (class "Default")
      (node (ref "M.2_SLOT") (pin "19") (pinfunction "19_19") (pintype "unspecified+no_connect"))
    )
    (net (code "89") (name "unconnected-(M.2_SLOT-Pad20)") (class "Default")
      (node (ref "M.2_SLOT") (pin "20") (pinfunction "20_20") (pintype "unspecified+no_connect"))
    )
    (net (code "90") (name "unconnected-(M.2_SLOT-Pad32)") (class "Default")
      (node (ref "M.2_SLOT") (pin "32") (pinfunction "32_32") (pintype "unspecified+no_connect"))
    )
    (net (code "91") (name "unconnected-(M.2_SLOT-Pad34)") (class "Default")
      (node (ref "M.2_SLOT") (pin "34") (pinfunction "34_34") (pintype "unspecified+no_connect"))
    )
    (net (code "92") (name "unconnected-(M.2_SLOT-Pad36)") (class "Default")
      (node (ref "M.2_SLOT") (pin "36") (pinfunction "36_36") (pintype "unspecified+no_connect"))
    )
    (net (code "93") (name "unconnected-(M.2_SLOT-Pad37)") (class "Default")
      (node (ref "M.2_SLOT") (pin "37") (pinfunction "37_37") (pintype "unspecified+no_connect"))
    )
    (net (code "94") (name "unconnected-(M.2_SLOT-Pad38)") (class "Default")
      (node (ref "M.2_SLOT") (pin "38") (pinfunction "38_38") (pintype "unspecified+no_connect"))
    )
    (net (code "95") (name "unconnected-(M.2_SLOT-Pad39)") (class "Default")
      (node (ref "M.2_SLOT") (pin "39") (pinfunction "39_39") (pintype "unspecified+no_connect"))
    )
    (net (code "96") (name "unconnected-(M.2_SLOT-Pad40)") (class "Default")
      (node (ref "M.2_SLOT") (pin "40") (pinfunction "40_40") (pintype "unspecified+no_connect"))
    )
    (net (code "97") (name "unconnected-(M.2_SLOT-Pad42)") (class "Default")
      (node (ref "M.2_SLOT") (pin "42") (pinfunction "42_42") (pintype "unspecified+no_connect"))
    )
    (net (code "98") (name "unconnected-(M.2_SLOT-Pad44)") (class "Default")
      (node (ref "M.2_SLOT") (pin "44") (pinfunction "44_44") (pintype "unspecified+no_connect"))
    )
    (net (code "99") (name "unconnected-(M.2_SLOT-Pad45)") (class "Default")
      (node (ref "M.2_SLOT") (pin "45") (pinfunction "45_45") (pintype "unspecified+no_connect"))
    )
    (net (code "100") (name "unconnected-(M.2_SLOT-Pad46)") (class "Default")
      (node (ref "M.2_SLOT") (pin "46") (pinfunction "46_46") (pintype "unspecified+no_connect"))
    )
    (net (code "101") (name "unconnected-(M.2_SLOT-Pad47)") (class "Default")
      (node (ref "M.2_SLOT") (pin "47") (pinfunction "47_47") (pintype "unspecified+no_connect"))
    )
    (net (code "102") (name "unconnected-(M.2_SLOT-Pad48)") (class "Default")
      (node (ref "M.2_SLOT") (pin "48") (pinfunction "48_48") (pintype "unspecified+no_connect"))
    )
    (net (code "103") (name "unconnected-(M.2_SLOT-Pad50)") (class "Default")
      (node (ref "M.2_SLOT") (pin "50") (pinfunction "50_50") (pintype "unspecified+no_connect"))
    )
    (net (code "104") (name "unconnected-(M.2_SLOT-Pad52)") (class "Default")
      (node (ref "M.2_SLOT") (pin "52") (pinfunction "52_52") (pintype "unspecified+no_connect"))
    )
    (net (code "105") (name "unconnected-(M.2_SLOT-Pad53)") (class "Default")
      (node (ref "M.2_SLOT") (pin "53") (pinfunction "53_53") (pintype "unspecified+no_connect"))
    )
    (net (code "106") (name "unconnected-(M.2_SLOT-Pad54)") (class "Default")
      (node (ref "M.2_SLOT") (pin "54") (pinfunction "54_54") (pintype "unspecified+no_connect"))
    )
    (net (code "107") (name "unconnected-(M.2_SLOT-Pad55)") (class "Default")
      (node (ref "M.2_SLOT") (pin "55") (pinfunction "55_55") (pintype "unspecified+no_connect"))
    )
    (net (code "108") (name "unconnected-(M.2_SLOT-Pad56)") (class "Default")
      (node (ref "M.2_SLOT") (pin "56") (pinfunction "56_56") (pintype "unspecified+no_connect"))
    )
    (net (code "109") (name "unconnected-(M.2_SLOT-Pad57)") (class "Default")
      (node (ref "M.2_SLOT") (pin "57") (pinfunction "57_57") (pintype "unspecified+no_connect"))
    )
    (net (code "110") (name "unconnected-(M.2_SLOT-Pad58)") (class "Default")
      (node (ref "M.2_SLOT") (pin "58") (pinfunction "58_58") (pintype "unspecified+no_connect"))
    )
    (net (code "111") (name "unconnected-(M.2_SLOT-Pad59)") (class "Default")
      (node (ref "M.2_SLOT") (pin "59") (pinfunction "59_59") (pintype "unspecified+no_connect"))
    )
    (net (code "112") (name "unconnected-(M.2_SLOT-Pad60)") (class "Default")
      (node (ref "M.2_SLOT") (pin "60") (pinfunction "60_60") (pintype "unspecified+no_connect"))
    )
    (net (code "113") (name "unconnected-(M.2_SLOT-Pad61)") (class "Default")
      (node (ref "M.2_SLOT") (pin "61") (pinfunction "61_61") (pintype "unspecified+no_connect"))
    )
    (net (code "114") (name "unconnected-(M.2_SLOT-Pad62)") (class "Default")
      (node (ref "M.2_SLOT") (pin "62") (pinfunction "62_62") (pintype "unspecified+no_connect"))
    )
    (net (code "115") (name "unconnected-(M.2_SLOT-Pad63)") (class "Default")
      (node (ref "M.2_SLOT") (pin "63") (pinfunction "63_63") (pintype "unspecified+no_connect"))
    )
    (net (code "116") (name "unconnected-(M.2_SLOT-Pad64)") (class "Default")
      (node (ref "M.2_SLOT") (pin "64") (pinfunction "64_64") (pintype "unspecified+no_connect"))
    )
    (net (code "117") (name "unconnected-(M.2_SLOT-Pad65)") (class "Default")
      (node (ref "M.2_SLOT") (pin "65") (pinfunction "65_65") (pintype "unspecified+no_connect"))
    )
    (net (code "118") (name "unconnected-(M.2_SLOT-Pad66)") (class "Default")
      (node (ref "M.2_SLOT") (pin "66") (pinfunction "66_66") (pintype "unspecified+no_connect"))
    )
    (net (code "119") (name "unconnected-(M.2_SLOT-Pad67)") (class "Default")
      (node (ref "M.2_SLOT") (pin "67") (pinfunction "67_67") (pintype "unspecified+no_connect"))
    )
    (net (code "120") (name "unconnected-(M.2_SLOT-Pad68)") (class "Default")
      (node (ref "M.2_SLOT") (pin "68") (pinfunction "68_68") (pintype "unspecified+no_connect"))
    )
    (net (code "121") (name "unconnected-(M.2_SLOT-Pad70)") (class "Default")
      (node (ref "M.2_SLOT") (pin "70") (pinfunction "70_70") (pintype "unspecified+no_connect"))
    )
    (net (code "122") (name "unconnected-(M.2_SLOT-Pad71)") (class "Default")
      (node (ref "M.2_SLOT") (pin "71") (pinfunction "71_71") (pintype "unspecified+no_connect"))
    )
    (net (code "123") (name "unconnected-(M.2_SLOT-Pad72)") (class "Default")
      (node (ref "M.2_SLOT") (pin "72") (pinfunction "72_72") (pintype "unspecified+no_connect"))
    )
    (net (code "124") (name "unconnected-(M.2_SLOT-Pad73)") (class "Default")
      (node (ref "M.2_SLOT") (pin "73") (pinfunction "73_73") (pintype "unspecified+no_connect"))
    )
    (net (code "125") (name "unconnected-(M.2_SLOT-Pad75)") (class "Default")
      (node (ref "M.2_SLOT") (pin "75") (pinfunction "75_75") (pintype "unspecified+no_connect"))
    )
    (net (code "126") (name "unconnected-(M.2_SLOT-Pad76)") (class "Default")
      (node (ref "M.2_SLOT") (pin "76") (pinfunction "76_76") (pintype "unspecified+no_connect"))
    )
    (net (code "127") (name "unconnected-(M.2_SLOT-Pad77)") (class "Default")
      (node (ref "M.2_SLOT") (pin "77") (pinfunction "77_77") (pintype "unspecified+no_connect"))
    )
    (net (code "128") (name "unconnected-(MUX_PCI/CAMERA-CEC-Pad15)") (class "Default")
      (node (ref "MUX_PCI/CAMERA") (pin "15") (pinfunction "CEC_15") (pintype "unspecified+no_connect"))
    )
    (net (code "129") (name "unconnected-(MUX_PCI/CAMERA-CEC_B-Pad20)") (class "Default")
      (node (ref "MUX_PCI/CAMERA") (pin "20") (pinfunction "CEC_B_20") (pintype "unspecified+no_connect"))
    )
    (net (code "130") (name "unconnected-(MUX_PCI/CAMERA-D0+B-Pad29)") (class "Default")
      (node (ref "MUX_PCI/CAMERA") (pin "29") (pinfunction "D0+B_29") (pintype "unspecified+no_connect"))
    )
    (net (code "131") (name "unconnected-(MUX_PCI/CAMERA-D0-B-Pad28)") (class "Default")
      (node (ref "MUX_PCI/CAMERA") (pin "28") (pinfunction "D0-B_28") (pintype "unspecified+no_connect"))
    )
    (net (code "132") (name "unconnected-(MUX_PCI/CAMERA-D1+B-Pad27)") (class "Default")
      (node (ref "MUX_PCI/CAMERA") (pin "27") (pinfunction "D1+B_27") (pintype "unspecified+no_connect"))
    )
    (net (code "133") (name "unconnected-(MUX_PCI/CAMERA-D1-B-Pad26)") (class "Default")
      (node (ref "MUX_PCI/CAMERA") (pin "26") (pinfunction "D1-B_26") (pintype "unspecified+no_connect"))
    )
    (net (code "134") (name "unconnected-(MUX_PCI/CAMERA-D2+B-Pad25)") (class "Default")
      (node (ref "MUX_PCI/CAMERA") (pin "25") (pinfunction "D2+B_25") (pintype "unspecified+no_connect"))
    )
    (net (code "135") (name "unconnected-(MUX_PCI/CAMERA-D2-B-Pad24)") (class "Default")
      (node (ref "MUX_PCI/CAMERA") (pin "24") (pinfunction "D2-B_24") (pintype "unspecified+no_connect"))
    )
    (net (code "136") (name "unconnected-(MUX_PCI/CAMERA-D3+B-Pad23)") (class "Default")
      (node (ref "MUX_PCI/CAMERA") (pin "23") (pinfunction "D3+B_23") (pintype "unspecified+no_connect"))
    )
    (net (code "137") (name "unconnected-(MUX_PCI/CAMERA-D3-B-Pad22)") (class "Default")
      (node (ref "MUX_PCI/CAMERA") (pin "22") (pinfunction "D3-B_22") (pintype "unspecified+no_connect"))
    )
    (net (code "138") (name "unconnected-(MUX_PCI/CAMERA-HPD-Pad14)") (class "Default")
      (node (ref "MUX_PCI/CAMERA") (pin "14") (pinfunction "HPD_14") (pintype "unspecified+no_connect"))
    )
    (net (code "139") (name "unconnected-(MUX_PCI/CAMERA-HPD_B-Pad21)") (class "Default")
      (node (ref "MUX_PCI/CAMERA") (pin "21") (pinfunction "HPD_B_21") (pintype "unspecified+no_connect"))
    )
    (net (code "140") (name "unconnected-(MUX_PCI/CAMERA-NC-Pad9)") (class "Default")
      (node (ref "MUX_PCI/CAMERA") (pin "9") (pinfunction "NC_9") (pintype "unspecified+no_connect"))
    )
    (net (code "141") (name "unconnected-(MUX_PCI/CAMERA-NC-Pad30)") (class "Default")
      (node (ref "MUX_PCI/CAMERA") (pin "30") (pinfunction "NC_30") (pintype "unspecified+no_connect"))
    )
    (net (code "142") (name "unconnected-(MUX_PCI/CAMERA-SCL_B-Pad40)") (class "Default")
      (node (ref "MUX_PCI/CAMERA") (pin "40") (pinfunction "SCL_B_40") (pintype "unspecified+no_connect"))
    )
    (net (code "143") (name "unconnected-(MUX_PCI/CAMERA-SDA_B-Pad39)") (class "Default")
      (node (ref "MUX_PCI/CAMERA") (pin "39") (pinfunction "SDA_B_39") (pintype "unspecified+no_connect"))
    )
    (net (code "144") (name "unconnected-(MUX_PCI/CAMERA-SEL1-Pad16)") (class "Default")
      (node (ref "MUX_PCI/CAMERA") (pin "16") (pinfunction "SEL1_16") (pintype "unspecified+no_connect"))
    )
    (net (code "145") (name "unconnected-(MUX_PCI/CAMERA-SEL2-Pad17)") (class "Default")
      (node (ref "MUX_PCI/CAMERA") (pin "17") (pinfunction "SEL2_17") (pintype "unspecified+no_connect"))
    )
    (net (code "146") (name "unconnected-(PROCESSOR_(RS485_SLAVE)-PA2-Pad27)") (class "Default")
      (node (ref "PROCESSOR_(RS485_SLAVE)") (pin "27") (pinfunction "PA2_27") (pintype "unspecified+no_connect"))
    )
    (net (code "147") (name "unconnected-(PROCESSOR_(RS485_SLAVE)-PA3-Pad28)") (class "Default")
      (node (ref "PROCESSOR_(RS485_SLAVE)") (pin "28") (pinfunction "PA3_28") (pintype "unspecified+no_connect"))
    )
    (net (code "148") (name "unconnected-(PROCESSOR_(RS485_SLAVE)-PA5-Pad30)") (class "Default")
      (node (ref "PROCESSOR_(RS485_SLAVE)") (pin "30") (pinfunction "PA5_30") (pintype "unspecified+no_connect"))
    )
    (net (code "149") (name "unconnected-(PROCESSOR_(RS485_SLAVE)-PA6-Pad31)") (class "Default")
      (node (ref "PROCESSOR_(RS485_SLAVE)") (pin "31") (pinfunction "PA6_31") (pintype "unspecified+no_connect"))
    )
    (net (code "150") (name "unconnected-(PROCESSOR_(RS485_SLAVE)-PA7-Pad32)") (class "Default")
      (node (ref "PROCESSOR_(RS485_SLAVE)") (pin "32") (pinfunction "PA7_32") (pintype "unspecified+no_connect"))
    )
    (net (code "151") (name "unconnected-(PROCESSOR_(RS485_SLAVE)-PA8-Pad5)") (class "Default")
      (node (ref "PROCESSOR_(RS485_SLAVE)") (pin "5") (pinfunction "PA8_5") (pintype "unspecified+no_connect"))
    )
    (net (code "152") (name "unconnected-(PROCESSOR_(RS485_SLAVE)-PA11-Pad8)") (class "Default")
      (node (ref "PROCESSOR_(RS485_SLAVE)") (pin "8") (pinfunction "PA11_8") (pintype "unspecified+no_connect"))
    )
    (net (code "153") (name "unconnected-(PROCESSOR_(RS485_SLAVE)-PA12-Pad9)") (class "Default")
      (node (ref "PROCESSOR_(RS485_SLAVE)") (pin "9") (pinfunction "PA12_9") (pintype "unspecified+no_connect"))
    )
    (net (code "154") (name "unconnected-(PROCESSOR_(RS485_SLAVE)-PA15-Pad10)") (class "Default")
      (node (ref "PROCESSOR_(RS485_SLAVE)") (pin "10") (pinfunction "PA15_10") (pintype "unspecified+no_connect"))
    )
    (net (code "155") (name "unconnected-(PROCESSOR_(RS485_SLAVE)-PB1-Pad34)") (class "Default")
      (node (ref "PROCESSOR_(RS485_SLAVE)") (pin "34") (pinfunction "PB1_34") (pintype "unspecified+no_connect"))
    )
    (net (code "156") (name "unconnected-(PROCESSOR_(RS485_SLAVE)-PB8-Pad16)") (class "Default")
      (node (ref "PROCESSOR_(RS485_SLAVE)") (pin "16") (pinfunction "PB8_16") (pintype "unspecified+no_connect"))
    )
    (net (code "157") (name "unconnected-(PROCESSOR_(RS485_SLAVE)-PB9-Pad17)") (class "Default")
      (node (ref "PROCESSOR_(RS485_SLAVE)") (pin "17") (pinfunction "PB9_17") (pintype "unspecified+no_connect"))
    )
    (net (code "158") (name "unconnected-(PROCESSOR_(RS485_SLAVE)-PB10-Pad35)") (class "Default")
      (node (ref "PROCESSOR_(RS485_SLAVE)") (pin "35") (pinfunction "PB10_35") (pintype "unspecified+no_connect"))
    )
    (net (code "159") (name "unconnected-(PROCESSOR_(RS485_SLAVE)-PB11-Pad36)") (class "Default")
      (node (ref "PROCESSOR_(RS485_SLAVE)") (pin "36") (pinfunction "PB11_36") (pintype "unspecified+no_connect"))
    )
    (net (code "160") (name "unconnected-(PROCESSOR_(RS485_SLAVE)-PB12-Pad1)") (class "Default")
      (node (ref "PROCESSOR_(RS485_SLAVE)") (pin "1") (pinfunction "PB12_1") (pintype "unspecified+no_connect"))
    )
    (net (code "161") (name "unconnected-(PROCESSOR_(RS485_SLAVE)-PB15-Pad4)") (class "Default")
      (node (ref "PROCESSOR_(RS485_SLAVE)") (pin "4") (pinfunction "PB15_4") (pintype "unspecified+no_connect"))
    )
    (net (code "162") (name "unconnected-(PROCESSOR_(RS485_SLAVE)-PC13-Pad22)") (class "Default")
      (node (ref "PROCESSOR_(RS485_SLAVE)") (pin "22") (pinfunction "PC13_22") (pintype "unspecified+no_connect"))
    )
    (net (code "163") (name "unconnected-(PROCESSOR_(RS485_SLAVE)-PC14-Pad23)") (class "Default")
      (node (ref "PROCESSOR_(RS485_SLAVE)") (pin "23") (pinfunction "PC14_23") (pintype "unspecified+no_connect"))
    )
    (net (code "164") (name "unconnected-(PROCESSOR_(RS485_SLAVE)-PC15-Pad24)") (class "Default")
      (node (ref "PROCESSOR_(RS485_SLAVE)") (pin "24") (pinfunction "PC15_24") (pintype "unspecified+no_connect"))
    )
    (net (code "165") (name "unconnected-(PROCESSOR_(RS485_SLAVE)-VBAT-Pad21)") (class "Default")
      (node (ref "PROCESSOR_(RS485_SLAVE)") (pin "21") (pinfunction "VBAT_21") (pintype "unspecified+no_connect"))
    )
  )
)
